# f4mpac.net
KiCad netlist of a schematic drawn in EAGLE
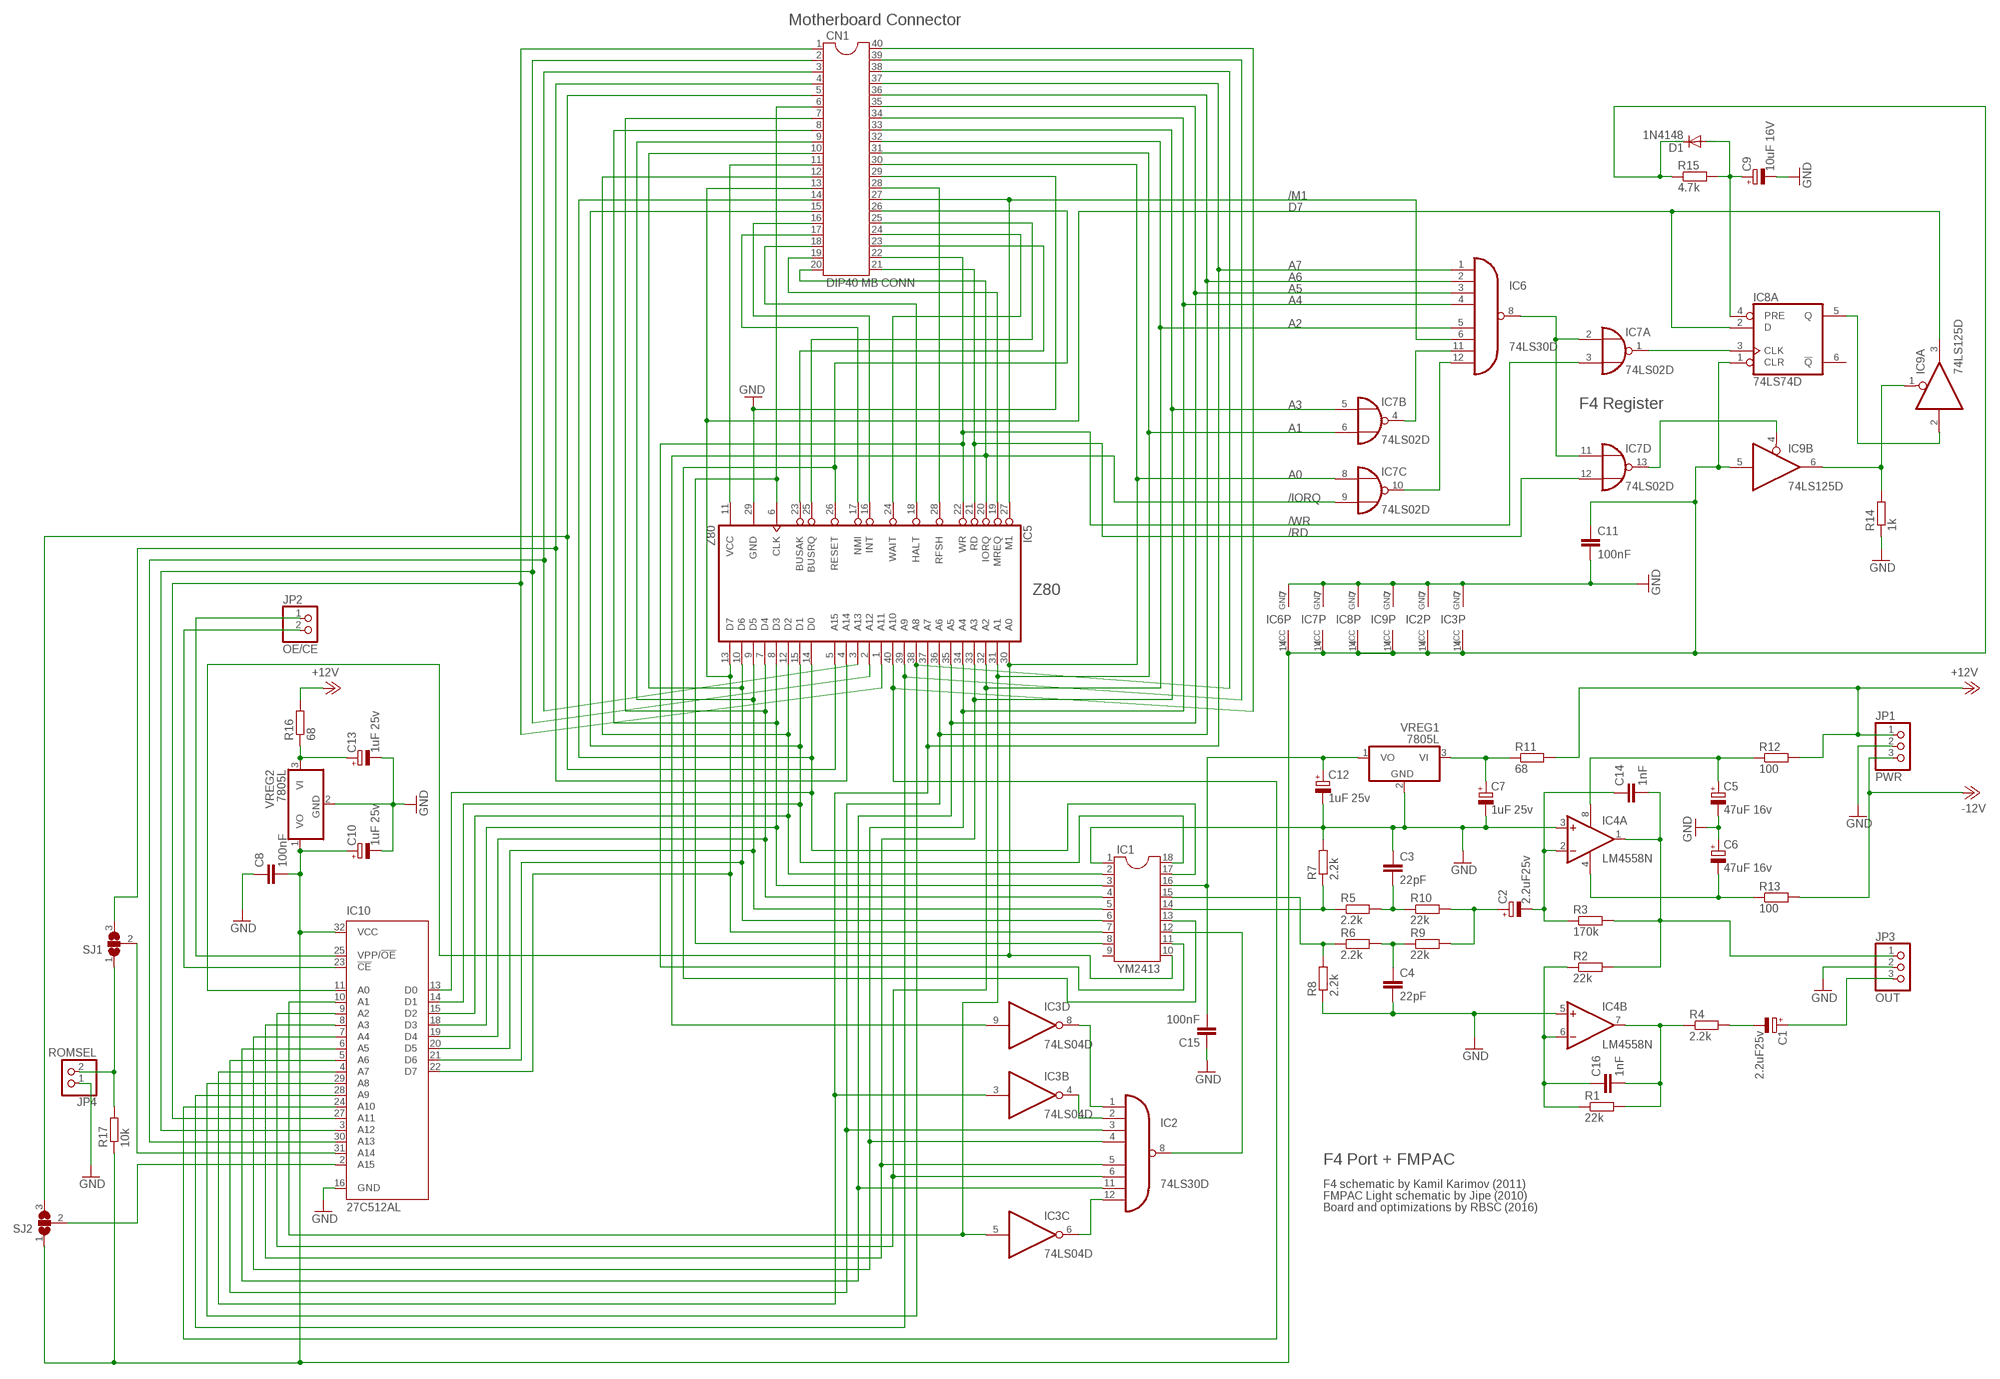
[diagram p0: schematic, sheet 1]

(export (version "E")
  (design (tool "Eeschema 10.0.6"))
  (components
    (comp (ref "C1")
      (value "2.2uF25v")
      (footprint "eagle-import:SMC_B")
      (libsource (lib "eagle-import") (part "CPOL-EUSMCB"))
    )
    (comp (ref "C2")
      (value "2.2uF25v")
      (footprint "eagle-import:SMC_B")
      (libsource (lib "eagle-import") (part "CPOL-EUSMCB"))
    )
    (comp (ref "C3")
      (value "22pF")
      (footprint "eagle-import:C0805")
      (libsource (lib "eagle-import") (part "C-EUC0805"))
    )
    (comp (ref "C4")
      (value "22pF")
      (footprint "eagle-import:C0805")
      (libsource (lib "eagle-import") (part "C-EUC0805"))
    )
    (comp (ref "C5")
      (value "47uF 16v")
      (footprint "eagle-import:SMC_C")
      (libsource (lib "eagle-import") (part "CPOL-EUSMCC"))
    )
    (comp (ref "C6")
      (value "47uF 16v")
      (footprint "eagle-import:SMC_C")
      (libsource (lib "eagle-import") (part "CPOL-EUSMCC"))
    )
    (comp (ref "C7")
      (value "1uF 25v")
      (footprint "eagle-import:SMC_B")
      (libsource (lib "eagle-import") (part "CPOL-EUSMCB"))
    )
    (comp (ref "C8")
      (value "100nF")
      (footprint "eagle-import:C0805")
      (libsource (lib "eagle-import") (part "C-EUC0805"))
    )
    (comp (ref "C9")
      (value "10uF 16V")
      (footprint "eagle-import:SMC_B")
      (libsource (lib "eagle-import") (part "CPOL-EUSMCB"))
    )
    (comp (ref "C10")
      (value "1uF 25v")
      (footprint "eagle-import:SMC_B")
      (libsource (lib "eagle-import") (part "CPOL-EUSMCB"))
    )
    (comp (ref "C11")
      (value "100nF")
      (footprint "eagle-import:C0805")
      (libsource (lib "eagle-import") (part "C-EUC0805"))
    )
    (comp (ref "C12")
      (value "1uF 25v")
      (footprint "eagle-import:SMC_B")
      (libsource (lib "eagle-import") (part "CPOL-EUSMCB"))
    )
    (comp (ref "C13")
      (value "1uF 25v")
      (footprint "eagle-import:SMC_B")
      (libsource (lib "eagle-import") (part "CPOL-EUSMCB"))
    )
    (comp (ref "C14")
      (value "1nF")
      (footprint "eagle-import:C0805")
      (libsource (lib "eagle-import") (part "C-EUC0805"))
    )
    (comp (ref "C15")
      (value "100nF")
      (footprint "eagle-import:C0805")
      (libsource (lib "eagle-import") (part "C-EUC0805"))
    )
    (comp (ref "C16")
      (value "1nF")
      (footprint "eagle-import:C0805")
      (libsource (lib "eagle-import") (part "C-EUC0805"))
    )
    (comp (ref "CN1")
      (value "DIP40 MB CONN")
      (footprint "eagle-import:DIL40")
      (libsource (lib "eagle-import") (part "DIL40"))
    )
    (comp (ref "D1")
      (value "1N4148")
      (footprint "eagle-import:MINIMELF")
      (libsource (lib "eagle-import") (part "DIODE-MINIMELF"))
    )
    (comp (ref "IC1")
      (value "YM2413")
      (footprint "eagle-import:DIL18")
      (libsource (lib "eagle-import") (part "DIL18"))
    )
    (comp (ref "IC2")
      (value "74LS30D")
      (footprint "eagle-import:SO14")
      (libsource (lib "eagle-import") (part "7430DLS"))
    )
    (comp (ref "IC3")
      (value "74LS04D")
      (footprint "eagle-import:SO14")
      (libsource (lib "eagle-import") (part "7404DLS"))
    )
    (comp (ref "IC4")
      (value "LM4558N")
      (footprint "eagle-import:DIL08")
      (libsource (lib "eagle-import") (part "4558NLM"))
    )
    (comp (ref "IC5")
      (value "Z80")
      (footprint "eagle-import:DIL40")
      (libsource (lib "eagle-import") (part "Z80CPU"))
    )
    (comp (ref "IC6")
      (value "74LS30D")
      (footprint "eagle-import:SO14")
      (libsource (lib "eagle-import") (part "7430DLS"))
    )
    (comp (ref "IC7")
      (value "74LS02D")
      (footprint "eagle-import:SO14")
      (libsource (lib "eagle-import") (part "7402DLS"))
    )
    (comp (ref "IC8")
      (value "74LS74D")
      (footprint "eagle-import:SO14")
      (libsource (lib "eagle-import") (part "7474DLS"))
    )
    (comp (ref "IC9")
      (value "74LS125D")
      (footprint "eagle-import:SO14")
      (libsource (lib "eagle-import") (part "74125DLS"))
    )
    (comp (ref "IC10")
      (value "27C512AL")
      (footprint "eagle-import:PLCC-32")
      (fields (field (name "MPN") "M27C512-90C1"))
      (libsource (lib "eagle-import") (part "27512ALC"))
    )
    (comp (ref "JP1")
      (value "PWR")
      (footprint "eagle-import:1X03_90")
      (libsource (lib "eagle-import") (part "PINHD-1X3/90"))
    )
    (comp (ref "JP2")
      (value "OE/CE")
      (footprint "eagle-import:1X02_90")
      (libsource (lib "eagle-import") (part "PINHD-1X2/90"))
    )
    (comp (ref "JP3")
      (value "OUT")
      (footprint "eagle-import:1X03_90")
      (libsource (lib "eagle-import") (part "PINHD-1X3/90"))
    )
    (comp (ref "JP4")
      (value "ROMSEL")
      (footprint "eagle-import:1X02_90")
      (libsource (lib "eagle-import") (part "PINHD-1X2/90"))
    )
    (comp (ref "R1")
      (value "22k")
      (footprint "eagle-import:R0805")
      (libsource (lib "eagle-import") (part "R-EU_R0805"))
    )
    (comp (ref "R2")
      (value "22k")
      (footprint "eagle-import:R0805")
      (libsource (lib "eagle-import") (part "R-EU_R0805"))
    )
    (comp (ref "R3")
      (value "170k")
      (footprint "eagle-import:R0805")
      (libsource (lib "eagle-import") (part "R-EU_R0805"))
    )
    (comp (ref "R4")
      (value "2.2k")
      (footprint "eagle-import:R0805")
      (libsource (lib "eagle-import") (part "R-EU_R0805"))
    )
    (comp (ref "R5")
      (value "2.2k")
      (footprint "eagle-import:R0805")
      (libsource (lib "eagle-import") (part "R-EU_R0805"))
    )
    (comp (ref "R6")
      (value "2.2k")
      (footprint "eagle-import:R0805")
      (libsource (lib "eagle-import") (part "R-EU_R0805"))
    )
    (comp (ref "R7")
      (value "2.2k")
      (footprint "eagle-import:R0805")
      (libsource (lib "eagle-import") (part "R-EU_R0805"))
    )
    (comp (ref "R8")
      (value "2.2k")
      (footprint "eagle-import:R0805")
      (libsource (lib "eagle-import") (part "R-EU_R0805"))
    )
    (comp (ref "R9")
      (value "22k")
      (footprint "eagle-import:R0805")
      (libsource (lib "eagle-import") (part "R-EU_R0805"))
    )
    (comp (ref "R10")
      (value "22k")
      (footprint "eagle-import:R0805")
      (libsource (lib "eagle-import") (part "R-EU_R0805"))
    )
    (comp (ref "R11")
      (value "68")
      (footprint "eagle-import:R0805")
      (libsource (lib "eagle-import") (part "R-EU_R0805"))
    )
    (comp (ref "R12")
      (value "100")
      (footprint "eagle-import:R0805")
      (libsource (lib "eagle-import") (part "R-EU_R0805"))
    )
    (comp (ref "R13")
      (value "100")
      (footprint "eagle-import:R0805")
      (libsource (lib "eagle-import") (part "R-EU_R0805"))
    )
    (comp (ref "R14")
      (value "1k")
      (footprint "eagle-import:R0805")
      (libsource (lib "eagle-import") (part "R-EU_R0805"))
    )
    (comp (ref "R15")
      (value "4.7k")
      (footprint "eagle-import:M0805")
      (libsource (lib "eagle-import") (part "R-EU_M0805"))
    )
    (comp (ref "R16")
      (value "68")
      (footprint "eagle-import:R0805")
      (libsource (lib "eagle-import") (part "R-EU_R0805"))
    )
    (comp (ref "R17")
      (value "10k")
      (footprint "eagle-import:R0805")
      (libsource (lib "eagle-import") (part "R-EU_R0805"))
    )
    (comp (ref "SJ1")
      (value "SJ2W")
      (footprint "eagle-import:SJ_2")
      (libsource (lib "eagle-import") (part "SJ2W"))
    )
    (comp (ref "SJ2")
      (value "SJ2W")
      (footprint "eagle-import:SJ_2")
      (libsource (lib "eagle-import") (part "SJ2W"))
    )
    (comp (ref "VREG1")
      (value "7805L")
      (footprint "eagle-import:TO92")
      (libsource (lib "eagle-import") (part "78L05"))
    )
    (comp (ref "VREG2")
      (value "7805L")
      (footprint "eagle-import:TO92")
      (libsource (lib "eagle-import") (part "78L05"))
    )
  )
  (nets
    (net (code "1") (name "+12V") (class "Default")
      (node (ref "JP1") (pin "1") (pinfunction "1_1") (pintype "passive"))
      (node (ref "R11") (pin "2") (pinfunction "2_2") (pintype "passive"))
      (node (ref "R12") (pin "2") (pinfunction "2_2") (pintype "passive"))
      (node (ref "R16") (pin "2") (pinfunction "2_2") (pintype "passive"))
    )
    (net (code "2") (name "-12V") (class "Default")
      (node (ref "JP1") (pin "3") (pinfunction "3_3") (pintype "passive"))
      (node (ref "R13") (pin "2") (pinfunction "2_2") (pintype "passive"))
    )
    (net (code "3") (name "GND") (class "Default")
      (node (ref "C10") (pin "-") (pinfunction "-_-") (pintype "passive"))
      (node (ref "C11") (pin "2") (pinfunction "2_2") (pintype "passive"))
      (node (ref "C12") (pin "-") (pinfunction "-_-") (pintype "passive"))
      (node (ref "C13") (pin "-") (pinfunction "-_-") (pintype "passive"))
      (node (ref "C15") (pin "1") (pinfunction "1_1") (pintype "passive"))
      (node (ref "C3") (pin "1") (pinfunction "1_1") (pintype "passive"))
      (node (ref "C4") (pin "2") (pinfunction "2_2") (pintype "passive"))
      (node (ref "C5") (pin "-") (pinfunction "-_-") (pintype "passive"))
      (node (ref "C6") (pin "+") (pinfunction "+_+") (pintype "passive"))
      (node (ref "C7") (pin "-") (pinfunction "-_-") (pintype "passive"))
      (node (ref "C8") (pin "1") (pinfunction "1_1") (pintype "passive"))
      (node (ref "C9") (pin "-") (pinfunction "-_-") (pintype "passive"))
      (node (ref "CN1") (pin "29") (pinfunction "29_29") (pintype "passive"))
      (node (ref "IC1") (pin "1") (pinfunction "1_1") (pintype "passive"))
      (node (ref "IC10") (pin "16") (pinfunction "GND_16") (pintype "power_in"))
      (node (ref "IC2") (pin "7") (pinfunction "GND_7") (pintype "power_in"))
      (node (ref "IC3") (pin "7") (pinfunction "GND_7") (pintype "power_in"))
      (node (ref "IC4") (pin "3") (pinfunction "+IN_3") (pintype "input"))
      (node (ref "IC4") (pin "5") (pinfunction "+IN_5") (pintype "input"))
      (node (ref "IC5") (pin "29") (pinfunction "GND_29") (pintype "power_in"))
      (node (ref "IC6") (pin "7") (pinfunction "GND_7") (pintype "power_in"))
      (node (ref "IC7") (pin "7") (pinfunction "GND_7") (pintype "power_in"))
      (node (ref "IC8") (pin "7") (pinfunction "GND_7") (pintype "power_in"))
      (node (ref "IC9") (pin "7") (pinfunction "GND_7") (pintype "power_in"))
      (node (ref "JP1") (pin "2") (pinfunction "2_2") (pintype "passive"))
      (node (ref "JP3") (pin "2") (pinfunction "2_2") (pintype "passive"))
      (node (ref "JP4") (pin "1") (pinfunction "1_1") (pintype "passive"))
      (node (ref "R14") (pin "1") (pinfunction "1_1") (pintype "passive"))
      (node (ref "R7") (pin "2") (pinfunction "2_2") (pintype "passive"))
      (node (ref "R8") (pin "1") (pinfunction "1_1") (pintype "passive"))
      (node (ref "VREG1") (pin "2") (pinfunction "GND_2") (pintype "passive"))
      (node (ref "VREG2") (pin "2") (pinfunction "GND_2") (pintype "passive"))
    )
    (net (code "4") (name "Net-(C1-Pad+)") (class "Default")
      (node (ref "C1") (pin "+") (pinfunction "+_+") (pintype "passive"))
      (node (ref "JP3") (pin "3") (pinfunction "3_3") (pintype "passive"))
    )
    (net (code "5") (name "Net-(C1-Pad-)") (class "Default")
      (node (ref "C1") (pin "-") (pinfunction "-_-") (pintype "passive"))
      (node (ref "R4") (pin "2") (pinfunction "2_2") (pintype "passive"))
    )
    (net (code "6") (name "Net-(C2-Pad+)") (class "Default")
      (node (ref "C2") (pin "+") (pinfunction "+_+") (pintype "passive"))
      (node (ref "R10") (pin "2") (pinfunction "2_2") (pintype "passive"))
      (node (ref "R9") (pin "2") (pinfunction "2_2") (pintype "passive"))
    )
    (net (code "7") (name "Net-(C3-Pad2)") (class "Default")
      (node (ref "C3") (pin "2") (pinfunction "2_2") (pintype "passive"))
      (node (ref "R10") (pin "1") (pinfunction "1_1") (pintype "passive"))
      (node (ref "R5") (pin "2") (pinfunction "2_2") (pintype "passive"))
    )
    (net (code "8") (name "Net-(C4-Pad1)") (class "Default")
      (node (ref "C4") (pin "1") (pinfunction "1_1") (pintype "passive"))
      (node (ref "R6") (pin "2") (pinfunction "2_2") (pintype "passive"))
      (node (ref "R9") (pin "1") (pinfunction "1_1") (pintype "passive"))
    )
    (net (code "9") (name "Net-(IC1-Pad14)") (class "Default")
      (node (ref "IC1") (pin "14") (pinfunction "14_14") (pintype "passive"))
      (node (ref "R5") (pin "1") (pinfunction "1_1") (pintype "passive"))
      (node (ref "R7") (pin "1") (pinfunction "1_1") (pintype "passive"))
    )
    (net (code "10") (name "Net-(IC1-Pad15)") (class "Default")
      (node (ref "IC1") (pin "15") (pinfunction "15_15") (pintype "passive"))
      (node (ref "R6") (pin "1") (pinfunction "1_1") (pintype "passive"))
      (node (ref "R8") (pin "2") (pinfunction "2_2") (pintype "passive"))
    )
    (net (code "11") (name "Net-(IC2A-I0)") (class "Default")
      (node (ref "IC2") (pin "1") (pinfunction "I0_1") (pintype "input"))
      (node (ref "IC3") (pin "8") (pinfunction "O_8") (pintype "output"))
    )
    (net (code "12") (name "Net-(IC2A-I1)") (class "Default")
      (node (ref "IC2") (pin "2") (pinfunction "I1_2") (pintype "input"))
      (node (ref "IC3") (pin "4") (pinfunction "O_4") (pintype "output"))
    )
    (net (code "13") (name "Net-(IC2A-I7)") (class "Default")
      (node (ref "IC2") (pin "12") (pinfunction "I7_12") (pintype "input"))
      (node (ref "IC3") (pin "6") (pinfunction "O_6") (pintype "output"))
    )
    (net (code "14") (name "Net-(IC2A-O)") (class "Default")
      (node (ref "IC1") (pin "12") (pinfunction "12_12") (pintype "passive"))
      (node (ref "IC2") (pin "8") (pinfunction "O_8") (pintype "output"))
    )
    (net (code "15") (name "Net-(IC3D-I)") (class "Default")
      (node (ref "CN1") (pin "20") (pinfunction "20_20") (pintype "passive"))
      (node (ref "IC3") (pin "9") (pinfunction "I_9") (pintype "input"))
      (node (ref "IC5") (pin "20") (pinfunction "IORQ_20") (pintype "output"))
      (node (ref "IC7") (pin "9") (pinfunction "I1_9") (pintype "input"))
    )
    (net (code "16") (name "Net-(IC4A--IN)") (class "Default")
      (node (ref "C14") (pin "1") (pinfunction "1_1") (pintype "passive"))
      (node (ref "C2") (pin "-") (pinfunction "-_-") (pintype "passive"))
      (node (ref "IC4") (pin "2") (pinfunction "-IN_2") (pintype "input"))
      (node (ref "R3") (pin "1") (pinfunction "1_1") (pintype "passive"))
    )
    (net (code "17") (name "Net-(IC4A-OUT)") (class "Default")
      (node (ref "C14") (pin "2") (pinfunction "2_2") (pintype "passive"))
      (node (ref "IC4") (pin "1") (pinfunction "OUT_1") (pintype "output"))
      (node (ref "JP3") (pin "1") (pinfunction "1_1") (pintype "passive"))
      (node (ref "R2") (pin "2") (pinfunction "2_2") (pintype "passive"))
      (node (ref "R3") (pin "2") (pinfunction "2_2") (pintype "passive"))
    )
    (net (code "18") (name "Net-(IC4B--IN)") (class "Default")
      (node (ref "C16") (pin "1") (pinfunction "1_1") (pintype "passive"))
      (node (ref "IC4") (pin "6") (pinfunction "-IN_6") (pintype "input"))
      (node (ref "R1") (pin "1") (pinfunction "1_1") (pintype "passive"))
      (node (ref "R2") (pin "1") (pinfunction "1_1") (pintype "passive"))
    )
    (net (code "19") (name "Net-(IC4B-OUT)") (class "Default")
      (node (ref "C16") (pin "2") (pinfunction "2_2") (pintype "passive"))
      (node (ref "IC4") (pin "7") (pinfunction "OUT_7") (pintype "output"))
      (node (ref "R1") (pin "2") (pinfunction "2_2") (pintype "passive"))
      (node (ref "R4") (pin "1") (pinfunction "1_1") (pintype "passive"))
    )
    (net (code "20") (name "Net-(IC4C-V+)") (class "Default")
      (node (ref "C5") (pin "+") (pinfunction "+_+") (pintype "passive"))
      (node (ref "IC4") (pin "8") (pinfunction "V+_8") (pintype "power_in"))
      (node (ref "R12") (pin "1") (pinfunction "1_1") (pintype "passive"))
    )
    (net (code "21") (name "Net-(IC4C-V-)") (class "Default")
      (node (ref "C6") (pin "-") (pinfunction "-_-") (pintype "passive"))
      (node (ref "IC4") (pin "4") (pinfunction "V-_4") (pintype "power_in"))
      (node (ref "R13") (pin "1") (pinfunction "1_1") (pintype "passive"))
    )
    (net (code "22") (name "Net-(IC5-A14)") (class "Default")
      (node (ref "CN1") (pin "4") (pinfunction "4_4") (pintype "passive"))
      (node (ref "IC5") (pin "4") (pinfunction "A14_4") (pintype "output"))
      (node (ref "SJ1") (pin "3") (pinfunction "3_3") (pintype "passive"))
    )
    (net (code "23") (name "Net-(IC5-A15)") (class "Default")
      (node (ref "CN1") (pin "5") (pinfunction "5_5") (pintype "passive"))
      (node (ref "IC5") (pin "5") (pinfunction "A15_5") (pintype "output"))
      (node (ref "SJ2") (pin "3") (pinfunction "3_3") (pintype "passive"))
    )
    (net (code "24") (name "Net-(IC5-BUSAK)") (class "Default")
      (node (ref "CN1") (pin "23") (pinfunction "23_23") (pintype "passive"))
      (node (ref "IC5") (pin "23") (pinfunction "BUSAK_23") (pintype "output"))
    )
    (net (code "25") (name "Net-(IC5-BUSRQ)") (class "Default")
      (node (ref "CN1") (pin "25") (pinfunction "25_25") (pintype "passive"))
      (node (ref "IC5") (pin "25") (pinfunction "BUSRQ_25") (pintype "input"))
    )
    (net (code "26") (name "Net-(IC5-CLK)") (class "Default")
      (node (ref "CN1") (pin "6") (pinfunction "6_6") (pintype "passive"))
      (node (ref "IC1") (pin "8") (pinfunction "8_8") (pintype "passive"))
      (node (ref "IC5") (pin "6") (pinfunction "CLK_6") (pintype "input"))
    )
    (net (code "27") (name "Net-(IC5-HALT)") (class "Default")
      (node (ref "CN1") (pin "18") (pinfunction "18_18") (pintype "passive"))
      (node (ref "IC5") (pin "18") (pinfunction "HALT_18") (pintype "output"))
    )
    (net (code "28") (name "Net-(IC5-INT)") (class "Default")
      (node (ref "CN1") (pin "16") (pinfunction "16_16") (pintype "passive"))
      (node (ref "IC5") (pin "16") (pinfunction "INT_16") (pintype "input"))
    )
    (net (code "29") (name "Net-(IC5-M1)") (class "Default")
      (node (ref "CN1") (pin "27") (pinfunction "27_27") (pintype "passive"))
      (node (ref "IC5") (pin "27") (pinfunction "M1_27") (pintype "output"))
      (node (ref "IC6") (pin "6") (pinfunction "I5_6") (pintype "input"))
    )
    (net (code "30") (name "Net-(IC5-MREQ)") (class "Default")
      (node (ref "CN1") (pin "19") (pinfunction "19_19") (pintype "passive"))
      (node (ref "IC5") (pin "19") (pinfunction "MREQ_19") (pintype "output"))
    )
    (net (code "31") (name "Net-(IC5-NMI)") (class "Default")
      (node (ref "CN1") (pin "17") (pinfunction "17_17") (pintype "passive"))
      (node (ref "IC5") (pin "17") (pinfunction "NMI_17") (pintype "input"))
    )
    (net (code "32") (name "Net-(IC5-RD)") (class "Default")
      (node (ref "CN1") (pin "21") (pinfunction "21_21") (pintype "passive"))
      (node (ref "IC5") (pin "21") (pinfunction "RD_21") (pintype "output"))
      (node (ref "IC7") (pin "12") (pinfunction "I1_12") (pintype "input"))
    )
    (net (code "33") (name "Net-(IC5-RESET)") (class "Default")
      (node (ref "CN1") (pin "26") (pinfunction "26_26") (pintype "passive"))
      (node (ref "IC1") (pin "13") (pinfunction "13_13") (pintype "passive"))
      (node (ref "IC5") (pin "26") (pinfunction "RESET_26") (pintype "input"))
    )
    (net (code "34") (name "Net-(IC5-RFSH)") (class "Default")
      (node (ref "CN1") (pin "28") (pinfunction "28_28") (pintype "passive"))
      (node (ref "IC5") (pin "28") (pinfunction "RFSH_28") (pintype "output"))
    )
    (net (code "35") (name "Net-(IC5-VCC)") (class "Default")
      (node (ref "CN1") (pin "11") (pinfunction "11_11") (pintype "passive"))
      (node (ref "IC5") (pin "11") (pinfunction "VCC_11") (pintype "power_in"))
    )
    (net (code "36") (name "Net-(IC5-WAIT)") (class "Default")
      (node (ref "CN1") (pin "24") (pinfunction "24_24") (pintype "passive"))
      (node (ref "IC5") (pin "24") (pinfunction "WAIT_24") (pintype "input"))
    )
    (net (code "37") (name "Net-(IC5-WR)") (class "Default")
      (node (ref "CN1") (pin "22") (pinfunction "22_22") (pintype "passive"))
      (node (ref "IC1") (pin "11") (pinfunction "11_11") (pintype "passive"))
      (node (ref "IC5") (pin "22") (pinfunction "WR_22") (pintype "output"))
      (node (ref "IC7") (pin "3") (pinfunction "I1_3") (pintype "input"))
    )
    (net (code "38") (name "Net-(IC6A-I6)") (class "Default")
      (node (ref "IC6") (pin "11") (pinfunction "I6_11") (pintype "input"))
      (node (ref "IC7") (pin "4") (pinfunction "O_4") (pintype "output"))
    )
    (net (code "39") (name "Net-(IC6A-I7)") (class "Default")
      (node (ref "IC6") (pin "12") (pinfunction "I7_12") (pintype "input"))
      (node (ref "IC7") (pin "10") (pinfunction "O_10") (pintype "output"))
    )
    (net (code "40") (name "Net-(IC6A-O)") (class "Default")
      (node (ref "IC6") (pin "8") (pinfunction "O_8") (pintype "output"))
      (node (ref "IC7") (pin "11") (pinfunction "I0_11") (pintype "input"))
      (node (ref "IC7") (pin "2") (pinfunction "I0_2") (pintype "input"))
    )
    (net (code "41") (name "Net-(IC7A-O)") (class "Default")
      (node (ref "IC7") (pin "1") (pinfunction "O_1") (pintype "output"))
      (node (ref "IC8") (pin "3") (pinfunction "CLK_3") (pintype "input"))
    )
    (net (code "42") (name "Net-(IC7D-O)") (class "Default")
      (node (ref "IC7") (pin "13") (pinfunction "O_13") (pintype "output"))
      (node (ref "IC9") (pin "4") (pinfunction "OE_4") (pintype "input"))
    )
    (net (code "43") (name "Net-(IC8A-PRE)") (class "Default")
      (node (ref "C9") (pin "+") (pinfunction "+_+") (pintype "passive"))
      (node (ref "D1") (pin "A") (pinfunction "A_A") (pintype "passive"))
      (node (ref "IC8") (pin "4") (pinfunction "PRE_4") (pintype "input"))
      (node (ref "R15") (pin "2") (pinfunction "2_2") (pintype "passive"))
    )
    (net (code "44") (name "Net-(IC8A-Q)") (class "Default")
      (node (ref "IC8") (pin "5") (pinfunction "Q_5") (pintype "output"))
      (node (ref "IC9") (pin "2") (pinfunction "I_2") (pintype "input"))
    )
    (net (code "45") (name "Net-(IC9A-OE)") (class "Default")
      (node (ref "IC9") (pin "1") (pinfunction "OE_1") (pintype "input"))
      (node (ref "IC9") (pin "6") (pinfunction "O_6") (pintype "tri_state"))
      (node (ref "R14") (pin "2") (pinfunction "2_2") (pintype "passive"))
    )
    (net (code "46") (name "Net-(IC10-A0)") (class "Default")
      (node (ref "CN1") (pin "30") (pinfunction "30_30") (pintype "passive"))
      (node (ref "IC1") (pin "10") (pinfunction "10_10") (pintype "passive"))
      (node (ref "IC10") (pin "11") (pinfunction "A0_11") (pintype "input"))
      (node (ref "IC5") (pin "30") (pinfunction "A0_30") (pintype "output"))
      (node (ref "IC7") (pin "8") (pinfunction "I0_8") (pintype "input"))
    )
    (net (code "47") (name "Net-(IC10-A1)") (class "Default")
      (node (ref "CN1") (pin "31") (pinfunction "31_31") (pintype "passive"))
      (node (ref "IC10") (pin "10") (pinfunction "A1_10") (pintype "input"))
      (node (ref "IC3") (pin "5") (pinfunction "I_5") (pintype "input"))
      (node (ref "IC5") (pin "31") (pinfunction "A1_31") (pintype "output"))
      (node (ref "IC7") (pin "6") (pinfunction "I1_6") (pintype "input"))
    )
    (net (code "48") (name "Net-(IC10-A2)") (class "Default")
      (node (ref "CN1") (pin "32") (pinfunction "32_32") (pintype "passive"))
      (node (ref "IC10") (pin "9") (pinfunction "A2_9") (pintype "input"))
      (node (ref "IC2") (pin "6") (pinfunction "I5_6") (pintype "input"))
      (node (ref "IC5") (pin "32") (pinfunction "A2_32") (pintype "output"))
      (node (ref "IC6") (pin "5") (pinfunction "I4_5") (pintype "input"))
    )
    (net (code "49") (name "Net-(IC10-A3)") (class "Default")
      (node (ref "CN1") (pin "33") (pinfunction "33_33") (pintype "passive"))
      (node (ref "IC10") (pin "8") (pinfunction "A3_8") (pintype "input"))
      (node (ref "IC2") (pin "5") (pinfunction "I4_5") (pintype "input"))
      (node (ref "IC5") (pin "33") (pinfunction "A3_33") (pintype "output"))
      (node (ref "IC7") (pin "5") (pinfunction "I0_5") (pintype "input"))
    )
    (net (code "50") (name "Net-(IC10-A4)") (class "Default")
      (node (ref "CN1") (pin "34") (pinfunction "34_34") (pintype "passive"))
      (node (ref "IC10") (pin "7") (pinfunction "A4_7") (pintype "input"))
      (node (ref "IC2") (pin "4") (pinfunction "I3_4") (pintype "input"))
      (node (ref "IC5") (pin "34") (pinfunction "A4_34") (pintype "output"))
      (node (ref "IC6") (pin "4") (pinfunction "I3_4") (pintype "input"))
    )
    (net (code "51") (name "Net-(IC10-A5)") (class "Default")
      (node (ref "CN1") (pin "35") (pinfunction "35_35") (pintype "passive"))
      (node (ref "IC10") (pin "6") (pinfunction "A5_6") (pintype "input"))
      (node (ref "IC2") (pin "11") (pinfunction "I6_11") (pintype "input"))
      (node (ref "IC5") (pin "35") (pinfunction "A5_35") (pintype "output"))
      (node (ref "IC6") (pin "3") (pinfunction "I2_3") (pintype "input"))
    )
    (net (code "52") (name "Net-(IC10-A6)") (class "Default")
      (node (ref "CN1") (pin "36") (pinfunction "36_36") (pintype "passive"))
      (node (ref "IC10") (pin "5") (pinfunction "A6_5") (pintype "input"))
      (node (ref "IC2") (pin "3") (pinfunction "I2_3") (pintype "input"))
      (node (ref "IC5") (pin "36") (pinfunction "A6_36") (pintype "output"))
      (node (ref "IC6") (pin "2") (pinfunction "I1_2") (pintype "input"))
    )
    (net (code "53") (name "Net-(IC10-A7)") (class "Default")
      (node (ref "CN1") (pin "37") (pinfunction "37_37") (pintype "passive"))
      (node (ref "IC10") (pin "4") (pinfunction "A7_4") (pintype "input"))
      (node (ref "IC3") (pin "3") (pinfunction "I_3") (pintype "input"))
      (node (ref "IC5") (pin "37") (pinfunction "A7_37") (pintype "output"))
      (node (ref "IC6") (pin "1") (pinfunction "I0_1") (pintype "input"))
    )
    (net (code "54") (name "Net-(IC10-A8)") (class "Default")
      (node (ref "CN1") (pin "38") (pinfunction "38_38") (pintype "passive"))
      (node (ref "IC10") (pin "29") (pinfunction "A8_29") (pintype "input"))
      (node (ref "IC5") (pin "38") (pinfunction "A8_38") (pintype "output"))
    )
    (net (code "55") (name "Net-(IC10-A9)") (class "Default")
      (node (ref "CN1") (pin "39") (pinfunction "39_39") (pintype "passive"))
      (node (ref "IC10") (pin "28") (pinfunction "A9_28") (pintype "input"))
      (node (ref "IC5") (pin "39") (pinfunction "A9_39") (pintype "output"))
    )
    (net (code "56") (name "Net-(IC10-A10)") (class "Default")
      (node (ref "CN1") (pin "40") (pinfunction "40_40") (pintype "passive"))
      (node (ref "IC10") (pin "24") (pinfunction "A10_24") (pintype "input"))
      (node (ref "IC5") (pin "40") (pinfunction "A10_40") (pintype "output"))
    )
    (net (code "57") (name "Net-(IC10-A11)") (class "Default")
      (node (ref "CN1") (pin "1") (pinfunction "1_1") (pintype "passive"))
      (node (ref "IC10") (pin "27") (pinfunction "A11_27") (pintype "input"))
      (node (ref "IC5") (pin "1") (pinfunction "A11_1") (pintype "output"))
    )
    (net (code "58") (name "Net-(IC10-A12)") (class "Default")
      (node (ref "CN1") (pin "2") (pinfunction "2_2") (pintype "passive"))
      (node (ref "IC10") (pin "3") (pinfunction "A12_3") (pintype "input"))
      (node (ref "IC5") (pin "2") (pinfunction "A12_2") (pintype "output"))
    )
    (net (code "59") (name "Net-(IC10-A13)") (class "Default")
      (node (ref "CN1") (pin "3") (pinfunction "3_3") (pintype "passive"))
      (node (ref "IC10") (pin "30") (pinfunction "A13_30") (pintype "input"))
      (node (ref "IC5") (pin "3") (pinfunction "A13_3") (pintype "output"))
    )
    (net (code "60") (name "Net-(IC10-A14)") (class "Default")
      (node (ref "IC10") (pin "31") (pinfunction "A14_31") (pintype "input"))
      (node (ref "SJ1") (pin "2") (pinfunction "2_2") (pintype "passive"))
    )
    (net (code "61") (name "Net-(IC10-A15)") (class "Default")
      (node (ref "IC10") (pin "2") (pinfunction "A15_2") (pintype "input"))
      (node (ref "SJ2") (pin "2") (pinfunction "2_2") (pintype "passive"))
    )
    (net (code "62") (name "Net-(IC10-D0)") (class "Default")
      (node (ref "CN1") (pin "14") (pinfunction "14_14") (pintype "passive"))
      (node (ref "IC1") (pin "17") (pinfunction "17_17") (pintype "passive"))
      (node (ref "IC10") (pin "13") (pinfunction "D0_13") (pintype "tri_state"))
      (node (ref "IC5") (pin "14") (pinfunction "D0_14") (pintype "bidirectional"))
    )
    (net (code "63") (name "Net-(IC10-D1)") (class "Default")
      (node (ref "CN1") (pin "15") (pinfunction "15_15") (pintype "passive"))
      (node (ref "IC1") (pin "18") (pinfunction "18_18") (pintype "passive"))
      (node (ref "IC10") (pin "14") (pinfunction "D1_14") (pintype "tri_state"))
      (node (ref "IC5") (pin "15") (pinfunction "D1_15") (pintype "bidirectional"))
    )
    (net (code "64") (name "Net-(IC10-D2)") (class "Default")
      (node (ref "CN1") (pin "12") (pinfunction "12_12") (pintype "passive"))
      (node (ref "IC1") (pin "2") (pinfunction "2_2") (pintype "passive"))
      (node (ref "IC10") (pin "15") (pinfunction "D2_15") (pintype "tri_state"))
      (node (ref "IC5") (pin "12") (pinfunction "D2_12") (pintype "bidirectional"))
    )
    (net (code "65") (name "Net-(IC10-D3)") (class "Default")
      (node (ref "CN1") (pin "8") (pinfunction "8_8") (pintype "passive"))
      (node (ref "IC1") (pin "3") (pinfunction "3_3") (pintype "passive"))
      (node (ref "IC10") (pin "18") (pinfunction "D3_18") (pintype "tri_state"))
      (node (ref "IC5") (pin "8") (pinfunction "D3_8") (pintype "bidirectional"))
    )
    (net (code "66") (name "Net-(IC10-D4)") (class "Default")
      (node (ref "CN1") (pin "7") (pinfunction "7_7") (pintype "passive"))
      (node (ref "IC1") (pin "4") (pinfunction "4_4") (pintype "passive"))
      (node (ref "IC10") (pin "19") (pinfunction "D4_19") (pintype "tri_state"))
      (node (ref "IC5") (pin "7") (pinfunction "D4_7") (pintype "bidirectional"))
    )
    (net (code "67") (name "Net-(IC10-D5)") (class "Default")
      (node (ref "CN1") (pin "9") (pinfunction "9_9") (pintype "passive"))
      (node (ref "IC1") (pin "5") (pinfunction "5_5") (pintype "passive"))
      (node (ref "IC10") (pin "20") (pinfunction "D5_20") (pintype "tri_state"))
      (node (ref "IC5") (pin "9") (pinfunction "D5_9") (pintype "bidirectional"))
    )
    (net (code "68") (name "Net-(IC10-D6)") (class "Default")
      (node (ref "CN1") (pin "10") (pinfunction "10_10") (pintype "passive"))
      (node (ref "IC1") (pin "6") (pinfunction "6_6") (pintype "passive"))
      (node (ref "IC10") (pin "21") (pinfunction "D6_21") (pintype "tri_state"))
      (node (ref "IC5") (pin "10") (pinfunction "D6_10") (pintype "bidirectional"))
    )
    (net (code "69") (name "Net-(IC10-D7)") (class "Default")
      (node (ref "CN1") (pin "13") (pinfunction "13_13") (pintype "passive"))
      (node (ref "IC1") (pin "7") (pinfunction "7_7") (pintype "passive"))
      (node (ref "IC10") (pin "22") (pinfunction "D7_22") (pintype "tri_state"))
      (node (ref "IC5") (pin "13") (pinfunction "D7_13") (pintype "bidirectional"))
      (node (ref "IC8") (pin "2") (pinfunction "D_2") (pintype "input"))
      (node (ref "IC9") (pin "3") (pinfunction "O_3") (pintype "tri_state"))
    )
    (net (code "70") (name "Net-(IC10-VCC)") (class "Default")
      (node (ref "C10") (pin "+") (pinfunction "+_+") (pintype "passive"))
      (node (ref "C11") (pin "1") (pinfunction "1_1") (pintype "passive"))
      (node (ref "C8") (pin "2") (pinfunction "2_2") (pintype "passive"))
      (node (ref "D1") (pin "C") (pinfunction "C_C") (pintype "passive"))
      (node (ref "IC10") (pin "32") (pinfunction "VCC_32") (pintype "power_in"))
      (node (ref "IC2") (pin "14") (pinfunction "VCC_14") (pintype "power_in"))
      (node (ref "IC3") (pin "14") (pinfunction "VCC_14") (pintype "power_in"))
      (node (ref "IC6") (pin "14") (pinfunction "VCC_14") (pintype "power_in"))
      (node (ref "IC7") (pin "14") (pinfunction "VCC_14") (pintype "power_in"))
      (node (ref "IC8") (pin "1") (pinfunction "CLR_1") (pintype "input"))
      (node (ref "IC8") (pin "14") (pinfunction "VCC_14") (pintype "power_in"))
      (node (ref "IC9") (pin "14") (pinfunction "VCC_14") (pintype "power_in"))
      (node (ref "IC9") (pin "5") (pinfunction "I_5") (pintype "input"))
      (node (ref "R15") (pin "1") (pinfunction "1_1") (pintype "passive"))
      (node (ref "R17") (pin "1") (pinfunction "1_1") (pintype "passive"))
      (node (ref "SJ2") (pin "1") (pinfunction "1_1") (pintype "passive"))
      (node (ref "VREG2") (pin "1") (pinfunction "VO_1") (pintype "passive"))
    )
    (net (code "71") (name "Net-(IC10-VPP{slash}~{OE})") (class "Default")
      (node (ref "IC10") (pin "25") (pinfunction "VPP/~{OE}_25") (pintype "input"))
      (node (ref "JP2") (pin "1") (pinfunction "1_1") (pintype "passive"))
    )
    (net (code "72") (name "Net-(IC10-~{CE})") (class "Default")
      (node (ref "IC10") (pin "23") (pinfunction "~{CE}_23") (pintype "input"))
      (node (ref "JP2") (pin "2") (pinfunction "2_2") (pintype "passive"))
    )
    (net (code "73") (name "Net-(JP4-Pad2)") (class "Default")
      (node (ref "JP4") (pin "2") (pinfunction "2_2") (pintype "passive"))
      (node (ref "R17") (pin "2") (pinfunction "2_2") (pintype "passive"))
      (node (ref "SJ1") (pin "1") (pinfunction "1_1") (pintype "passive"))
    )
    (net (code "74") (name "Net-(VREG1-VI)") (class "Default")
      (node (ref "C7") (pin "+") (pinfunction "+_+") (pintype "passive"))
      (node (ref "R11") (pin "1") (pinfunction "1_1") (pintype "passive"))
      (node (ref "VREG1") (pin "3") (pinfunction "VI_3") (pintype "input"))
    )
    (net (code "75") (name "Net-(VREG1-VO)") (class "Default")
      (node (ref "C12") (pin "+") (pinfunction "+_+") (pintype "passive"))
      (node (ref "C15") (pin "2") (pinfunction "2_2") (pintype "passive"))
      (node (ref "IC1") (pin "16") (pinfunction "16_16") (pintype "passive"))
      (node (ref "VREG1") (pin "1") (pinfunction "VO_1") (pintype "passive"))
    )
    (net (code "76") (name "Net-(VREG2-VI)") (class "Default")
      (node (ref "C13") (pin "+") (pinfunction "+_+") (pintype "passive"))
      (node (ref "R16") (pin "1") (pinfunction "1_1") (pintype "passive"))
      (node (ref "VREG2") (pin "3") (pinfunction "VI_3") (pintype "input"))
    )
    (net (code "77") (name "unconnected-(IC1-Pad9)") (class "Default")
      (node (ref "IC1") (pin "9") (pinfunction "9_9") (pintype "passive"))
    )
    (net (code "78") (name "unconnected-(IC8A-~{Q}-Pad6)") (class "Default")
      (node (ref "IC8") (pin "6") (pinfunction "~{Q}_6") (pintype "output"))
    )
  )
)
